# untitled.net
KiCad netlist of a schematic drawn in EAGLE
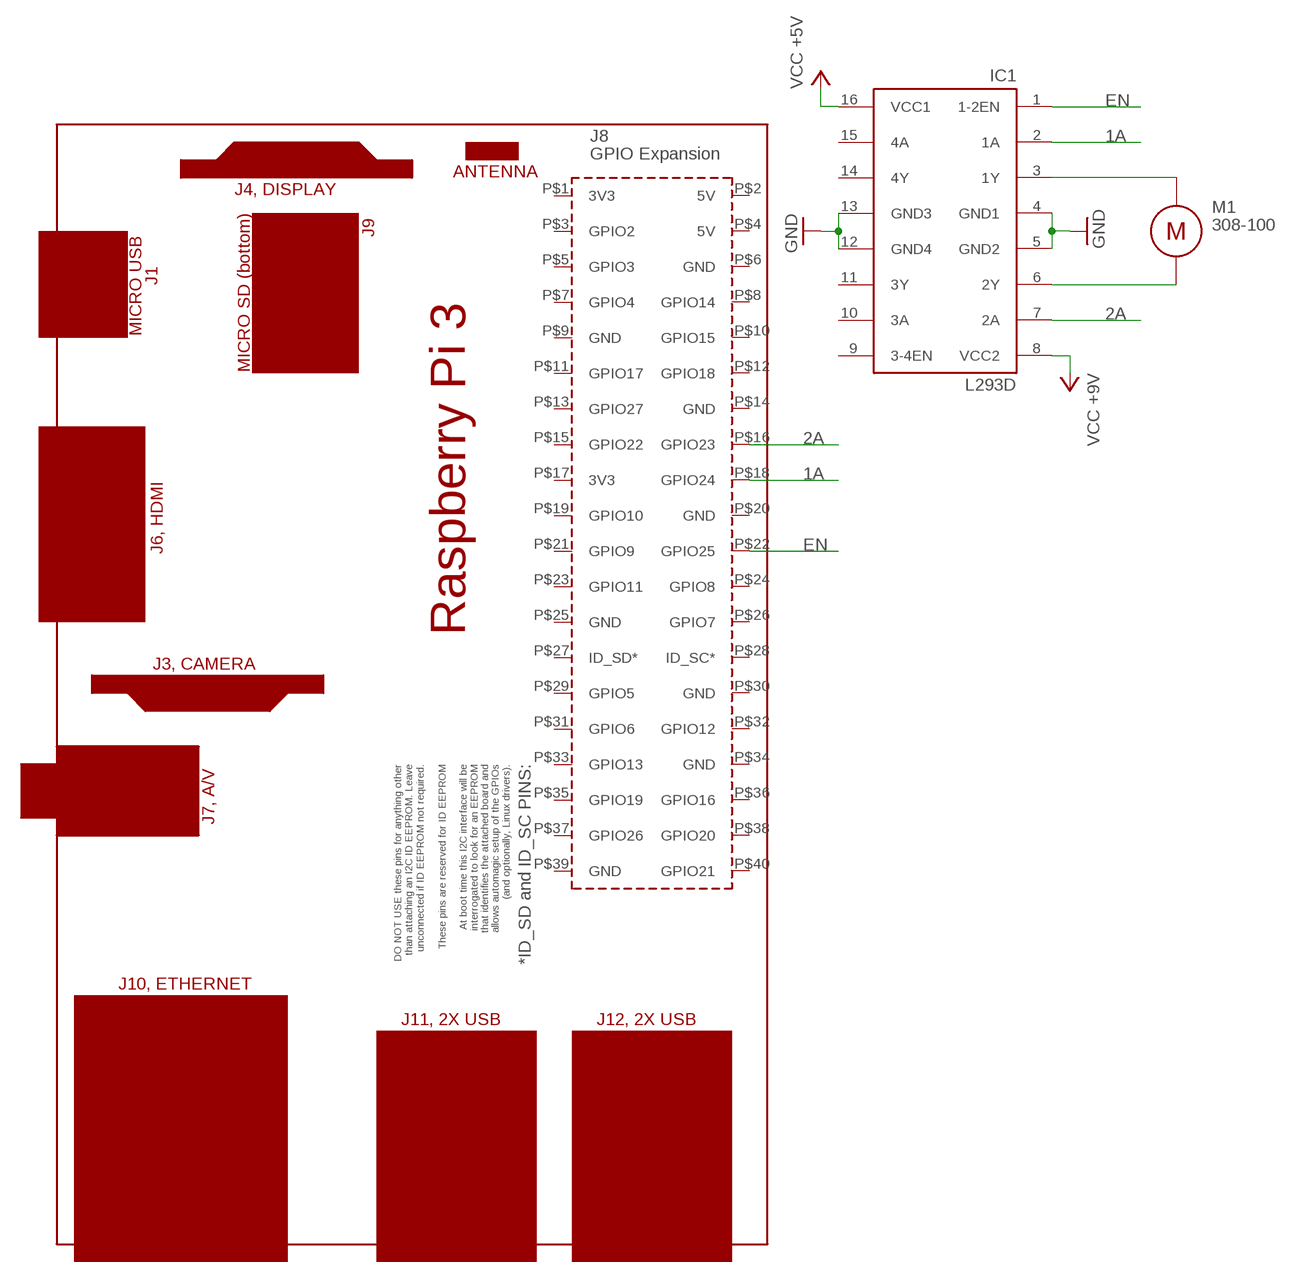
[diagram p0: schematic, sheet 1]

(export (version "E")
  (design (tool "Eeschema 10.0.6"))
  (components
    (comp (ref "IC1")
      (value "L293D")
      (footprint "eagle-import:DIL16")
      (libsource (lib "eagle-import") (part "L293D"))
    )
    (comp (ref "M1")
      (value "308-100")
      (footprint "eagle-import:308-100")
      (libsource (lib "eagle-import") (part "308-100"))
    )
    (comp (ref "PCB1")
      (value "RPI3RPI3")
      (footprint "eagle-import:RPI3")
      (libsource (lib "eagle-import") (part "RPI3RPI3"))
    )
  )
  (nets
    (net (code "1") (name "/1A") (class "Default")
      (node (ref "IC1") (pin "2") (pinfunction "1A_2") (pintype "input"))
      (node (ref "PCB1") (pin "P$18") (pinfunction "GPIO24_P$18") (pintype "bidirectional"))
    )
    (net (code "2") (name "/2A") (class "Default")
      (node (ref "IC1") (pin "7") (pinfunction "2A_7") (pintype "input"))
      (node (ref "PCB1") (pin "P$16") (pinfunction "GPIO23_P$16") (pintype "bidirectional"))
    )
    (net (code "3") (name "/EN") (class "Default")
      (node (ref "IC1") (pin "1") (pinfunction "1-2EN_1") (pintype "input"))
      (node (ref "PCB1") (pin "P$22") (pinfunction "GPIO25_P$22") (pintype "bidirectional"))
    )
    (net (code "4") (name "GND") (class "Default")
      (node (ref "IC1") (pin "12") (pinfunction "GND4_12") (pintype "power_in"))
      (node (ref "IC1") (pin "13") (pinfunction "GND3_13") (pintype "power_in"))
      (node (ref "IC1") (pin "4") (pinfunction "GND1_4") (pintype "power_in"))
      (node (ref "IC1") (pin "5") (pinfunction "GND2_5") (pintype "power_in"))
    )
    (net (code "5") (name "Net-(IC1-1Y)") (class "Default")
      (node (ref "IC1") (pin "3") (pinfunction "1Y_3") (pintype "output"))
      (node (ref "M1") (pin "POS") (pinfunction "POS_POS") (pintype "bidirectional"))
    )
    (net (code "6") (name "Net-(IC1-2Y)") (class "Default")
      (node (ref "IC1") (pin "6") (pinfunction "2Y_6") (pintype "output"))
      (node (ref "M1") (pin "NEG") (pinfunction "NEG_NEG") (pintype "bidirectional"))
    )
    (net (code "7") (name "VCC +5V") (class "Default")
      (node (ref "IC1") (pin "16") (pinfunction "VCC1_16") (pintype "power_in"))
      (node (ref "IC1") (pin "8") (pinfunction "VCC2_8") (pintype "power_in"))
    )
    (net (code "8") (name "unconnected-(IC1-3-4EN-Pad9)") (class "Default")
      (node (ref "IC1") (pin "9") (pinfunction "3-4EN_9") (pintype "input"))
    )
    (net (code "9") (name "unconnected-(IC1-3A-Pad10)") (class "Default")
      (node (ref "IC1") (pin "10") (pinfunction "3A_10") (pintype "input"))
    )
    (net (code "10") (name "unconnected-(IC1-3Y-Pad11)") (class "Default")
      (node (ref "IC1") (pin "11") (pinfunction "3Y_11") (pintype "output"))
    )
    (net (code "11") (name "unconnected-(IC1-4A-Pad15)") (class "Default")
      (node (ref "IC1") (pin "15") (pinfunction "4A_15") (pintype "input"))
    )
    (net (code "12") (name "unconnected-(IC1-4Y-Pad14)") (class "Default")
      (node (ref "IC1") (pin "14") (pinfunction "4Y_14") (pintype "output"))
    )
    (net (code "13") (name "unconnected-(PCB1-3V3-PadP$1)") (class "Default")
      (node (ref "PCB1") (pin "P$1") (pinfunction "3V3_P$1") (pintype "bidirectional"))
    )
    (net (code "14") (name "unconnected-(PCB1-3V3-PadP$17)") (class "Default")
      (node (ref "PCB1") (pin "P$17") (pinfunction "3V3_P$17") (pintype "bidirectional"))
    )
    (net (code "15") (name "unconnected-(PCB1-5V-PadP$2)") (class "Default")
      (node (ref "PCB1") (pin "P$2") (pinfunction "5V_P$2") (pintype "bidirectional"))
    )
    (net (code "16") (name "unconnected-(PCB1-5V-PadP$4)") (class "Default")
      (node (ref "PCB1") (pin "P$4") (pinfunction "5V_P$4") (pintype "bidirectional"))
    )
    (net (code "17") (name "unconnected-(PCB1-GND-PadP$6)") (class "Default")
      (node (ref "PCB1") (pin "P$6") (pinfunction "GND_P$6") (pintype "bidirectional"))
    )
    (net (code "18") (name "unconnected-(PCB1-GND-PadP$9)") (class "Default")
      (node (ref "PCB1") (pin "P$9") (pinfunction "GND_P$9") (pintype "bidirectional"))
    )
    (net (code "19") (name "unconnected-(PCB1-GND-PadP$14)") (class "Default")
      (node (ref "PCB1") (pin "P$14") (pinfunction "GND_P$14") (pintype "bidirectional"))
    )
    (net (code "20") (name "unconnected-(PCB1-GND-PadP$20)") (class "Default")
      (node (ref "PCB1") (pin "P$20") (pinfunction "GND_P$20") (pintype "bidirectional"))
    )
    (net (code "21") (name "unconnected-(PCB1-GND-PadP$25)") (class "Default")
      (node (ref "PCB1") (pin "P$25") (pinfunction "GND_P$25") (pintype "bidirectional"))
    )
    (net (code "22") (name "unconnected-(PCB1-GND-PadP$30)") (class "Default")
      (node (ref "PCB1") (pin "P$30") (pinfunction "GND_P$30") (pintype "bidirectional"))
    )
    (net (code "23") (name "unconnected-(PCB1-GND-PadP$34)") (class "Default")
      (node (ref "PCB1") (pin "P$34") (pinfunction "GND_P$34") (pintype "bidirectional"))
    )
    (net (code "24") (name "unconnected-(PCB1-GND-PadP$39)") (class "Default")
      (node (ref "PCB1") (pin "P$39") (pinfunction "GND_P$39") (pintype "bidirectional"))
    )
    (net (code "25") (name "unconnected-(PCB1-GPIO2-PadP$3)") (class "Default")
      (node (ref "PCB1") (pin "P$3") (pinfunction "GPIO2_P$3") (pintype "bidirectional"))
    )
    (net (code "26") (name "unconnected-(PCB1-GPIO3-PadP$5)") (class "Default")
      (node (ref "PCB1") (pin "P$5") (pinfunction "GPIO3_P$5") (pintype "bidirectional"))
    )
    (net (code "27") (name "unconnected-(PCB1-GPIO4-PadP$7)") (class "Default")
      (node (ref "PCB1") (pin "P$7") (pinfunction "GPIO4_P$7") (pintype "bidirectional"))
    )
    (net (code "28") (name "unconnected-(PCB1-GPIO5-PadP$29)") (class "Default")
      (node (ref "PCB1") (pin "P$29") (pinfunction "GPIO5_P$29") (pintype "bidirectional"))
    )
    (net (code "29") (name "unconnected-(PCB1-GPIO6-PadP$31)") (class "Default")
      (node (ref "PCB1") (pin "P$31") (pinfunction "GPIO6_P$31") (pintype "bidirectional"))
    )
    (net (code "30") (name "unconnected-(PCB1-GPIO7-PadP$26)") (class "Default")
      (node (ref "PCB1") (pin "P$26") (pinfunction "GPIO7_P$26") (pintype "bidirectional"))
    )
    (net (code "31") (name "unconnected-(PCB1-GPIO8-PadP$24)") (class "Default")
      (node (ref "PCB1") (pin "P$24") (pinfunction "GPIO8_P$24") (pintype "bidirectional"))
    )
    (net (code "32") (name "unconnected-(PCB1-GPIO9-PadP$21)") (class "Default")
      (node (ref "PCB1") (pin "P$21") (pinfunction "GPIO9_P$21") (pintype "bidirectional"))
    )
    (net (code "33") (name "unconnected-(PCB1-GPIO10-PadP$19)") (class "Default")
      (node (ref "PCB1") (pin "P$19") (pinfunction "GPIO10_P$19") (pintype "bidirectional"))
    )
    (net (code "34") (name "unconnected-(PCB1-GPIO11-PadP$23)") (class "Default")
      (node (ref "PCB1") (pin "P$23") (pinfunction "GPIO11_P$23") (pintype "bidirectional"))
    )
    (net (code "35") (name "unconnected-(PCB1-GPIO12-PadP$32)") (class "Default")
      (node (ref "PCB1") (pin "P$32") (pinfunction "GPIO12_P$32") (pintype "bidirectional"))
    )
    (net (code "36") (name "unconnected-(PCB1-GPIO13-PadP$33)") (class "Default")
      (node (ref "PCB1") (pin "P$33") (pinfunction "GPIO13_P$33") (pintype "bidirectional"))
    )
    (net (code "37") (name "unconnected-(PCB1-GPIO14-PadP$8)") (class "Default")
      (node (ref "PCB1") (pin "P$8") (pinfunction "GPIO14_P$8") (pintype "bidirectional"))
    )
    (net (code "38") (name "unconnected-(PCB1-GPIO15-PadP$10)") (class "Default")
      (node (ref "PCB1") (pin "P$10") (pinfunction "GPIO15_P$10") (pintype "bidirectional"))
    )
    (net (code "39") (name "unconnected-(PCB1-GPIO16-PadP$36)") (class "Default")
      (node (ref "PCB1") (pin "P$36") (pinfunction "GPIO16_P$36") (pintype "bidirectional"))
    )
    (net (code "40") (name "unconnected-(PCB1-GPIO17-PadP$11)") (class "Default")
      (node (ref "PCB1") (pin "P$11") (pinfunction "GPIO17_P$11") (pintype "bidirectional"))
    )
    (net (code "41") (name "unconnected-(PCB1-GPIO18-PadP$12)") (class "Default")
      (node (ref "PCB1") (pin "P$12") (pinfunction "GPIO18_P$12") (pintype "bidirectional"))
    )
    (net (code "42") (name "unconnected-(PCB1-GPIO19-PadP$35)") (class "Default")
      (node (ref "PCB1") (pin "P$35") (pinfunction "GPIO19_P$35") (pintype "bidirectional"))
    )
    (net (code "43") (name "unconnected-(PCB1-GPIO20-PadP$38)") (class "Default")
      (node (ref "PCB1") (pin "P$38") (pinfunction "GPIO20_P$38") (pintype "bidirectional"))
    )
    (net (code "44") (name "unconnected-(PCB1-GPIO21-PadP$40)") (class "Default")
      (node (ref "PCB1") (pin "P$40") (pinfunction "GPIO21_P$40") (pintype "bidirectional"))
    )
    (net (code "45") (name "unconnected-(PCB1-GPIO22-PadP$15)") (class "Default")
      (node (ref "PCB1") (pin "P$15") (pinfunction "GPIO22_P$15") (pintype "bidirectional"))
    )
    (net (code "46") (name "unconnected-(PCB1-GPIO26-PadP$37)") (class "Default")
      (node (ref "PCB1") (pin "P$37") (pinfunction "GPIO26_P$37") (pintype "bidirectional"))
    )
    (net (code "47") (name "unconnected-(PCB1-GPIO27-PadP$13)") (class "Default")
      (node (ref "PCB1") (pin "P$13") (pinfunction "GPIO27_P$13") (pintype "bidirectional"))
    )
    (net (code "48") (name "unconnected-(PCB1-ID_SC*-PadP$28)") (class "Default")
      (node (ref "PCB1") (pin "P$28") (pinfunction "ID_SC*_P$28") (pintype "bidirectional"))
    )
    (net (code "49") (name "unconnected-(PCB1-ID_SD*-PadP$27)") (class "Default")
      (node (ref "PCB1") (pin "P$27") (pinfunction "ID_SD*_P$27") (pintype "bidirectional"))
    )
  )
)
